# MCU.net
KiCad netlist of a schematic drawn in Altium Designer
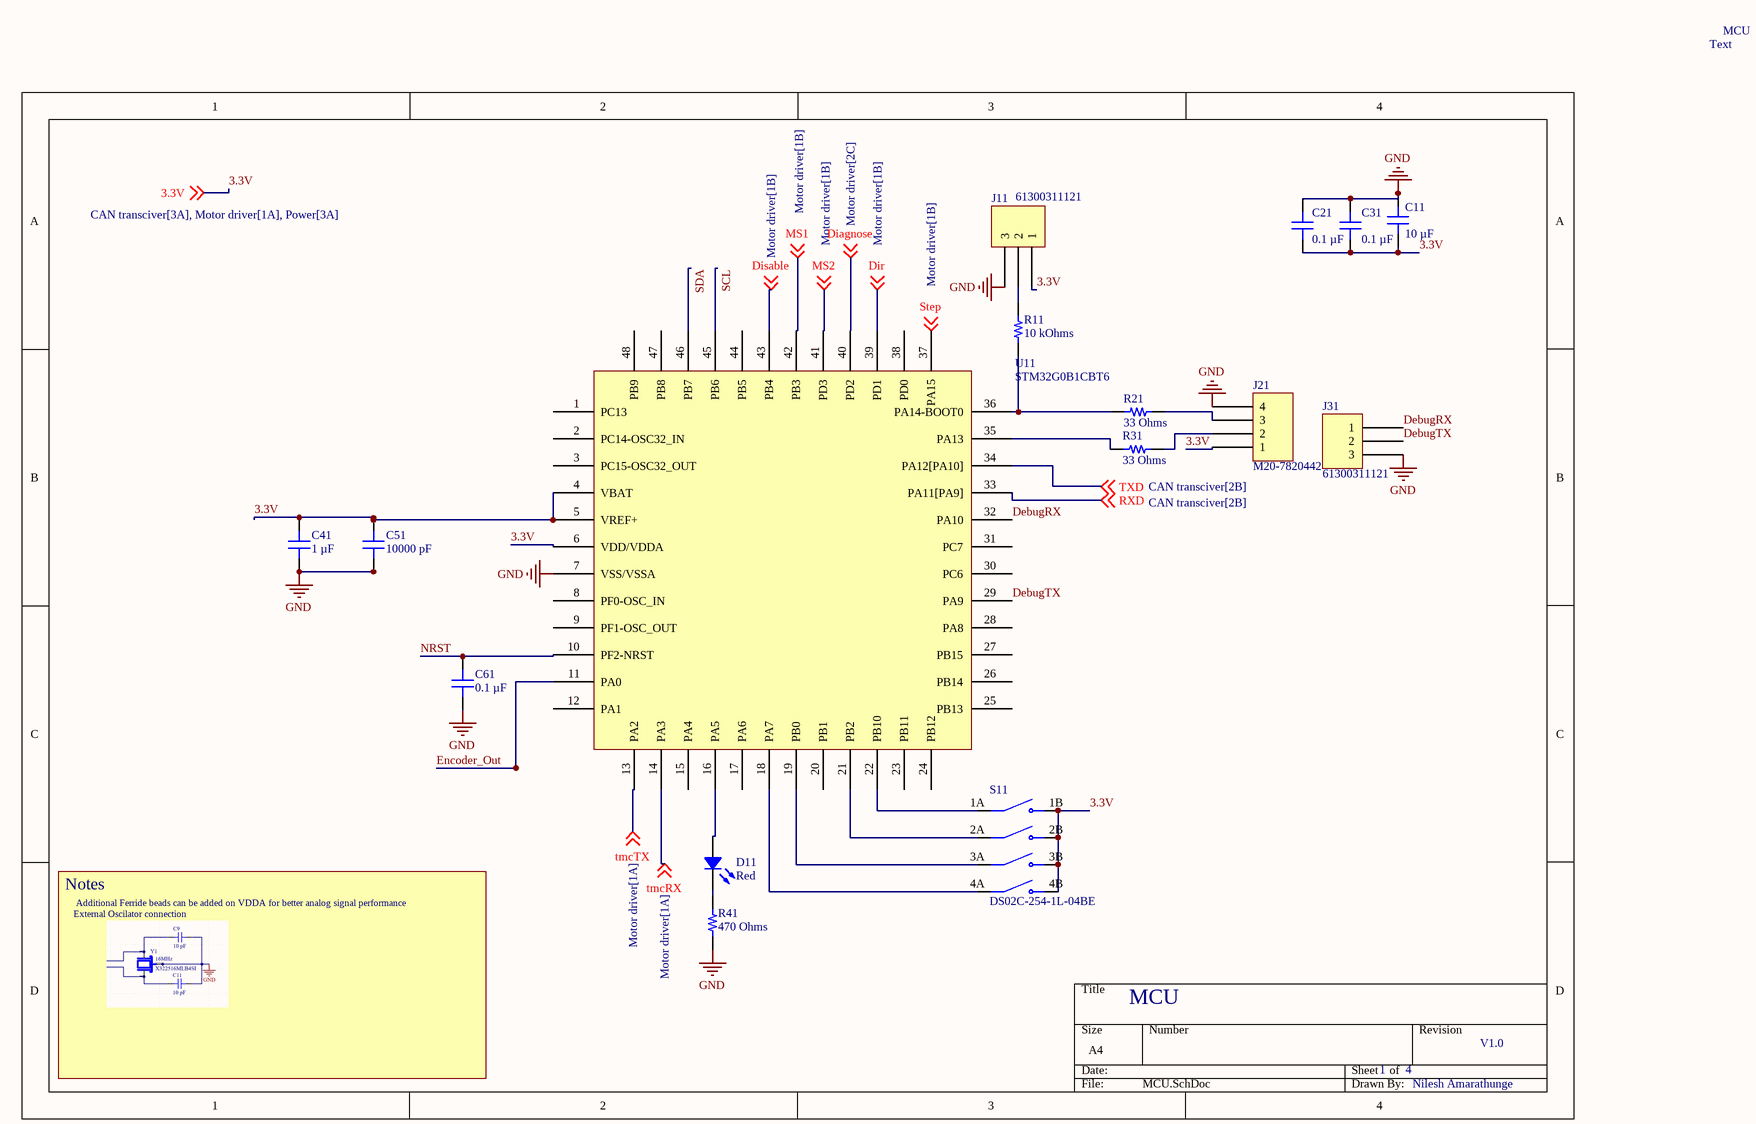
[diagram p0: MCU.SchDoc]

(export (version "E")
  (design (tool "Eeschema 10.0.6"))
  (components
    (comp (ref "C11")
      (value "10 µF")
      (footprint "CAP 0805_2012")
      (description "CAP CER 10UF 10V X7R 0805")
      (fields
        (field (name "PART NUMBER") "CL21B106KPQNNNE")
        (field (name "CAPACITANCE") "10 µF")
        (field (name "MANUFACTURER") "Samsung Electro-Mechanics")
      )
      (libsource (lib "Celestial Altium Library - altium_library") (part "Capacitor"))
    )
    (comp (ref "C21")
      (value "0.1 µF")
      (footprint "CAP 0805_2012")
      (description "CAP CER 0.1UF 50V X7R 0805")
      (fields
        (field (name "PART NUMBER") "CC0805KRX7R9BB104")
        (field (name "CAPACITANCE") "0.1 µF")
        (field (name "MANUFACTURER") "Yageo")
      )
      (libsource (lib "Celestial Altium Library - altium_library") (part "Capacitor"))
    )
    (comp (ref "C31")
      (value "0.1 µF")
      (footprint "CAP 0805_2012")
      (description "CAP CER 0.1UF 50V X7R 0805")
      (fields
        (field (name "PART NUMBER") "CC0805KRX7R9BB104")
        (field (name "CAPACITANCE") "0.1 µF")
        (field (name "MANUFACTURER") "Yageo")
      )
      (libsource (lib "Celestial Altium Library - altium_library") (part "Capacitor"))
    )
    (comp (ref "C41")
      (value "1 µF")
      (footprint "CAP 0805_2012")
      (description "CAP CER 1UF 16V X7R 0805")
      (fields
        (field (name "PART NUMBER") "CL21B105KOFNNNE")
        (field (name "CAPACITANCE") "1 µF")
        (field (name "MANUFACTURER") "Samsung Electro-Mechanics")
      )
      (libsource (lib "Celestial Altium Library - altium_library") (part "Capacitor"))
    )
    (comp (ref "C51")
      (value "10000 pF")
      (footprint "CAP 0805_2012")
      (description "CAP CER 10000PF 50V X7R 0805")
      (fields
        (field (name "PART NUMBER") "CL21B103KBANNNC")
        (field (name "CAPACITANCE") "10000 pF")
        (field (name "MANUFACTURER") "Samsung Electro-Mechanics")
      )
      (libsource (lib "Celestial Altium Library - altium_library") (part "Capacitor"))
    )
    (comp (ref "C61")
      (value "0.1 µF")
      (footprint "CAP 0805_2012")
      (description "CAP CER 0.1UF 50V X7R 0805")
      (fields
        (field (name "PART NUMBER") "CC0805KRX7R9BB104")
        (field (name "CAPACITANCE") "0.1 µF")
        (field (name "MANUFACTURER") "Yageo")
      )
      (libsource (lib "Celestial Altium Library - altium_library") (part "Capacitor"))
    )
    (comp (ref "D11")
      (value "Red")
      (footprint "LED 0805_2012 RED")
      (description "LED RED 0805 SMD")
      (fields (field (name "PART NUMBER") "5990110007F") (field (name "MANUFACTURER") "Dialight"))
      (libsource (lib "Celestial Altium Library - altium_library") (part "LED"))
    )
    (comp (ref "J11")
      (value "61300311121")
      (footprint "WURTH WE-PHD 61300311121")
      (description "CONN HEADER VERT 3POS 2.54MM")
      (fields (field (name "MANUFACTURER") "Würth Elektronik"))
      (libsource (lib "") (part "3 Pin_1"))
    )
    (comp (ref "J21")
      (value "M20-7820442")
      (footprint "HARWIN M20-7820445")
      (description "CONN RCPT 4POS 0.1 GOLD PCB")
      (fields (field (name "MANUFACTURER") "Harwin Inc."))
      (libsource (lib "Celestial Altium Library - altium_library") (part "4 Pin"))
    )
    (comp (ref "J31")
      (value "61300311121")
      (footprint "WURTH WE-PHD 61300311121")
      (description "CONN HEADER VERT 3POS 2.54MM")
      (fields (field (name "MANUFACTURER") "Würth Elektronik"))
      (libsource (lib "Celestial Altium Library - altium_library") (part "3 Pin"))
    )
    (comp (ref "R11")
      (value "10 kOhms")
      (footprint "YAGEO RES 0805_2012")
      (description "RES 10K OHM 1% 1/8W 0805")
      (fields (field (name "PART NUMBER") "RC0805FR-0710KL") (field (name "MANUFACTURER") "Yageo"))
      (libsource (lib "Celestial Altium Library - altium_library") (part "Resistor"))
    )
    (comp (ref "R21")
      (value "33 Ohms")
      (footprint "RES 0805_2012")
      (description "RES 33 OHM 1% 1/2W 0805")
      (fields (field (name "PART NUMBER") "SR0805FR-4733RL") (field (name "MANUFACTURER") "Yageo"))
      (libsource (lib "Celestial Altium Library - altium_library") (part "Resistor"))
    )
    (comp (ref "R31")
      (value "33 Ohms")
      (footprint "RES 0805_2012")
      (description "RES 33 OHM 1% 1/2W 0805")
      (fields (field (name "PART NUMBER") "SR0805FR-4733RL") (field (name "MANUFACTURER") "Yageo"))
      (libsource (lib "Celestial Altium Library - altium_library") (part "Resistor"))
    )
    (comp (ref "R41")
      (value "470 Ohms")
      (footprint "RES 0805_2012")
      (description "RES SMD 470 OHM 0.1% 1/4W 0805")
      (fields
        (field (name "PART NUMBER") "ERJ-PB6B4700V")
        (field (name "MANUFACTURER") "Panasonic Electronic Components")
      )
      (libsource (lib "Celestial Altium Library - altium_library") (part "Resistor"))
    )
    (comp (ref "S11")
      (value "DS02C-254-1L-04BE")
      (footprint "SW_DS02C-254-1L-04BE")
      (fields (field (name "MF") "Same Sky") (field (name "LCSC PART #") "C5123702"))
      (libsource (lib "DS02C-254-1L-04BE") (part "DS02C-254-1L-04BE"))
    )
    (comp (ref "U11")
      (value "STM32G0B1CBT6")
      (footprint "QFP50P900X900X160-48N")
      (fields (field (name "LCSC PART #") "C2847904"))
      (libsource (lib "STM32G0B1CBT6") (part "STM32G0B1CBT6"))
    )
  )
  (nets
    (net (code "1") (name "/DebugRX") (class "Default")
      (node (ref "J31") (pin "1") (pinfunction "1_1") (pintype "passive"))
      (node (ref "U11") (pin "32") (pinfunction "PA10_32") (pintype "passive"))
    )
    (net (code "2") (name "/DebugTX") (class "Default")
      (node (ref "J31") (pin "2") (pinfunction "2_2") (pintype "passive"))
      (node (ref "U11") (pin "29") (pinfunction "PA9_29") (pintype "passive"))
    )
    (net (code "3") (name "/Encoder_Out") (class "Default")
      (node (ref "U11") (pin "11") (pinfunction "PA0_11") (pintype "passive"))
    )
    (net (code "4") (name "/NRST") (class "Default")
      (node (ref "C61") (pin "1") (pinfunction "1_1") (pintype "passive"))
      (node (ref "U11") (pin "10") (pinfunction "PF2-NRST_10") (pintype "passive"))
    )
    (net (code "5") (name "/SCL") (class "Default")
      (node (ref "U11") (pin "45") (pinfunction "PB6_45") (pintype "passive"))
    )
    (net (code "6") (name "/SDA") (class "Default")
      (node (ref "U11") (pin "46") (pinfunction "PB7_46") (pintype "passive"))
    )
    (net (code "7") (name "3.3V") (class "Default")
      (node (ref "C11") (pin "1") (pinfunction "1_1") (pintype "passive"))
      (node (ref "C21") (pin "1") (pinfunction "1_1") (pintype "passive"))
      (node (ref "C31") (pin "1") (pinfunction "1_1") (pintype "passive"))
      (node (ref "C41") (pin "1") (pinfunction "1_1") (pintype "passive"))
      (node (ref "C51") (pin "1") (pinfunction "1_1") (pintype "passive"))
      (node (ref "J11") (pin "1") (pinfunction "1_1") (pintype "passive"))
      (node (ref "J21") (pin "1") (pinfunction "1_1") (pintype "passive"))
      (node (ref "S11") (pin "1B") (pinfunction "NO1_1B") (pintype "passive"))
      (node (ref "S11") (pin "2B") (pinfunction "NO2_2B") (pintype "passive"))
      (node (ref "S11") (pin "3B") (pinfunction "NO3_3B") (pintype "passive"))
      (node (ref "S11") (pin "4B") (pinfunction "NO4_4B") (pintype "passive"))
      (node (ref "U11") (pin "4") (pinfunction "VBAT_4") (pintype "passive"))
      (node (ref "U11") (pin "5") (pinfunction "VREF+_5") (pintype "passive"))
      (node (ref "U11") (pin "6") (pinfunction "VDD/VDDA_6") (pintype "passive"))
    )
    (net (code "8") (name "Diagnose") (class "Default")
      (node (ref "U11") (pin "40") (pinfunction "PD2_40") (pintype "passive"))
    )
    (net (code "9") (name "Dir") (class "Default")
      (node (ref "U11") (pin "39") (pinfunction "PD1_39") (pintype "passive"))
    )
    (net (code "10") (name "Disable") (class "Default")
      (node (ref "U11") (pin "43") (pinfunction "PB4_43") (pintype "passive"))
    )
    (net (code "11") (name "GND") (class "Default")
      (node (ref "C11") (pin "2") (pinfunction "2_2") (pintype "passive"))
      (node (ref "C21") (pin "2") (pinfunction "2_2") (pintype "passive"))
      (node (ref "C31") (pin "2") (pinfunction "2_2") (pintype "passive"))
      (node (ref "C41") (pin "2") (pinfunction "2_2") (pintype "passive"))
      (node (ref "C51") (pin "2") (pinfunction "2_2") (pintype "passive"))
      (node (ref "C61") (pin "2") (pinfunction "2_2") (pintype "passive"))
      (node (ref "J11") (pin "3") (pinfunction "3_3") (pintype "passive"))
      (node (ref "J21") (pin "4") (pinfunction "4_4") (pintype "passive"))
      (node (ref "J31") (pin "3") (pinfunction "3_3") (pintype "passive"))
      (node (ref "R41") (pin "1") (pinfunction "1_1") (pintype "passive"))
      (node (ref "U11") (pin "7") (pinfunction "VSS/VSSA_7") (pintype "passive"))
    )
    (net (code "12") (name "MS1") (class "Default")
      (node (ref "U11") (pin "42") (pinfunction "PB3_42") (pintype "passive"))
    )
    (net (code "13") (name "MS2") (class "Default")
      (node (ref "U11") (pin "41") (pinfunction "PD3_41") (pintype "passive"))
    )
    (net (code "14") (name "Net-(D11-Pad2)") (class "Default")
      (node (ref "D11") (pin "2") (pinfunction "2_2") (pintype "passive"))
      (node (ref "R41") (pin "2") (pinfunction "2_2") (pintype "passive"))
    )
    (net (code "15") (name "Net-(J11-Pad2)") (class "Default")
      (node (ref "J11") (pin "2") (pinfunction "2_2") (pintype "passive"))
      (node (ref "R11") (pin "1") (pinfunction "1_1") (pintype "passive"))
    )
    (net (code "16") (name "Net-(J21-Pad2)") (class "Default")
      (node (ref "J21") (pin "2") (pinfunction "2_2") (pintype "passive"))
      (node (ref "R31") (pin "2") (pinfunction "2_2") (pintype "passive"))
    )
    (net (code "17") (name "Net-(J21-Pad3)") (class "Default")
      (node (ref "J21") (pin "3") (pinfunction "3_3") (pintype "passive"))
      (node (ref "R21") (pin "2") (pinfunction "2_2") (pintype "passive"))
    )
    (net (code "18") (name "Net-(S11-COM1)") (class "Default")
      (node (ref "S11") (pin "1A") (pinfunction "COM1_1A") (pintype "passive"))
      (node (ref "U11") (pin "22") (pinfunction "PB10_22") (pintype "passive"))
    )
    (net (code "19") (name "Net-(S11-COM2)") (class "Default")
      (node (ref "S11") (pin "2A") (pinfunction "COM2_2A") (pintype "passive"))
      (node (ref "U11") (pin "21") (pinfunction "PB2_21") (pintype "passive"))
    )
    (net (code "20") (name "Net-(S11-COM3)") (class "Default")
      (node (ref "S11") (pin "3A") (pinfunction "COM3_3A") (pintype "passive"))
      (node (ref "U11") (pin "19") (pinfunction "PB0_19") (pintype "passive"))
    )
    (net (code "21") (name "Net-(S11-COM4)") (class "Default")
      (node (ref "S11") (pin "4A") (pinfunction "COM4_4A") (pintype "passive"))
      (node (ref "U11") (pin "18") (pinfunction "PA7_18") (pintype "passive"))
    )
    (net (code "22") (name "Net-(U11-PA5)") (class "Default")
      (node (ref "D11") (pin "1") (pinfunction "1_1") (pintype "passive"))
      (node (ref "U11") (pin "16") (pinfunction "PA5_16") (pintype "passive"))
    )
    (net (code "23") (name "Net-(U11-PA13)") (class "Default")
      (node (ref "R31") (pin "1") (pinfunction "1_1") (pintype "passive"))
      (node (ref "U11") (pin "35") (pinfunction "PA13_35") (pintype "passive"))
    )
    (net (code "24") (name "Net-(U11-PA14-BOOT0)") (class "Default")
      (node (ref "R11") (pin "2") (pinfunction "2_2") (pintype "passive"))
      (node (ref "R21") (pin "1") (pinfunction "1_1") (pintype "passive"))
      (node (ref "U11") (pin "36") (pinfunction "PA14-BOOT0_36") (pintype "passive"))
    )
    (net (code "25") (name "RXD") (class "Default")
      (node (ref "U11") (pin "33") (pinfunction "PA11[PA9]_33") (pintype "passive"))
    )
    (net (code "26") (name "Step") (class "Default")
      (node (ref "U11") (pin "37") (pinfunction "PA15_37") (pintype "passive"))
    )
    (net (code "27") (name "TXD") (class "Default")
      (node (ref "U11") (pin "34") (pinfunction "PA12[PA10]_34") (pintype "passive"))
    )
    (net (code "28") (name "tmcRX") (class "Default")
      (node (ref "U11") (pin "14") (pinfunction "PA3_14") (pintype "passive"))
    )
    (net (code "29") (name "tmcTX") (class "Default")
      (node (ref "U11") (pin "13") (pinfunction "PA2_13") (pintype "passive"))
    )
    (net (code "30") (name "unconnected-(U11-PA1-Pad12)") (class "Default")
      (node (ref "U11") (pin "12") (pinfunction "PA1_12") (pintype "passive"))
    )
    (net (code "31") (name "unconnected-(U11-PA4-Pad15)") (class "Default")
      (node (ref "U11") (pin "15") (pinfunction "PA4_15") (pintype "passive"))
    )
    (net (code "32") (name "unconnected-(U11-PA6-Pad17)") (class "Default")
      (node (ref "U11") (pin "17") (pinfunction "PA6_17") (pintype "passive"))
    )
    (net (code "33") (name "unconnected-(U11-PA8-Pad28)") (class "Default")
      (node (ref "U11") (pin "28") (pinfunction "PA8_28") (pintype "passive"))
    )
    (net (code "34") (name "unconnected-(U11-PB1-Pad20)") (class "Default")
      (node (ref "U11") (pin "20") (pinfunction "PB1_20") (pintype "passive"))
    )
    (net (code "35") (name "unconnected-(U11-PB5-Pad44)") (class "Default")
      (node (ref "U11") (pin "44") (pinfunction "PB5_44") (pintype "passive"))
    )
    (net (code "36") (name "unconnected-(U11-PB8-Pad47)") (class "Default")
      (node (ref "U11") (pin "47") (pinfunction "PB8_47") (pintype "passive"))
    )
    (net (code "37") (name "unconnected-(U11-PB9-Pad48)") (class "Default")
      (node (ref "U11") (pin "48") (pinfunction "PB9_48") (pintype "passive"))
    )
    (net (code "38") (name "unconnected-(U11-PB11-Pad23)") (class "Default")
      (node (ref "U11") (pin "23") (pinfunction "PB11_23") (pintype "passive"))
    )
    (net (code "39") (name "unconnected-(U11-PB12-Pad24)") (class "Default")
      (node (ref "U11") (pin "24") (pinfunction "PB12_24") (pintype "passive"))
    )
    (net (code "40") (name "unconnected-(U11-PB13-Pad25)") (class "Default")
      (node (ref "U11") (pin "25") (pinfunction "PB13_25") (pintype "passive"))
    )
    (net (code "41") (name "unconnected-(U11-PB14-Pad26)") (class "Default")
      (node (ref "U11") (pin "26") (pinfunction "PB14_26") (pintype "passive"))
    )
    (net (code "42") (name "unconnected-(U11-PB15-Pad27)") (class "Default")
      (node (ref "U11") (pin "27") (pinfunction "PB15_27") (pintype "passive"))
    )
    (net (code "43") (name "unconnected-(U11-PC6-Pad30)") (class "Default")
      (node (ref "U11") (pin "30") (pinfunction "PC6_30") (pintype "passive"))
    )
    (net (code "44") (name "unconnected-(U11-PC7-Pad31)") (class "Default")
      (node (ref "U11") (pin "31") (pinfunction "PC7_31") (pintype "passive"))
    )
    (net (code "45") (name "unconnected-(U11-PC13-Pad1)") (class "Default")
      (node (ref "U11") (pin "1") (pinfunction "PC13_1") (pintype "passive"))
    )
    (net (code "46") (name "unconnected-(U11-PC14-OSC32_IN-Pad2)") (class "Default")
      (node (ref "U11") (pin "2") (pinfunction "PC14-OSC32_IN_2") (pintype "passive"))
    )
    (net (code "47") (name "unconnected-(U11-PC15-OSC32_OUT-Pad3)") (class "Default")
      (node (ref "U11") (pin "3") (pinfunction "PC15-OSC32_OUT_3") (pintype "passive"))
    )
    (net (code "48") (name "unconnected-(U11-PD0-Pad38)") (class "Default")
      (node (ref "U11") (pin "38") (pinfunction "PD0_38") (pintype "passive"))
    )
    (net (code "49") (name "unconnected-(U11-PF0-OSC_IN-Pad8)") (class "Default")
      (node (ref "U11") (pin "8") (pinfunction "PF0-OSC_IN_8") (pintype "passive"))
    )
    (net (code "50") (name "unconnected-(U11-PF1-OSC_OUT-Pad9)") (class "Default")
      (node (ref "U11") (pin "9") (pinfunction "PF1-OSC_OUT_9") (pintype "passive"))
    )
  )
)
